# Sheet1.net
KiCad netlist of a schematic drawn in Altium Designer
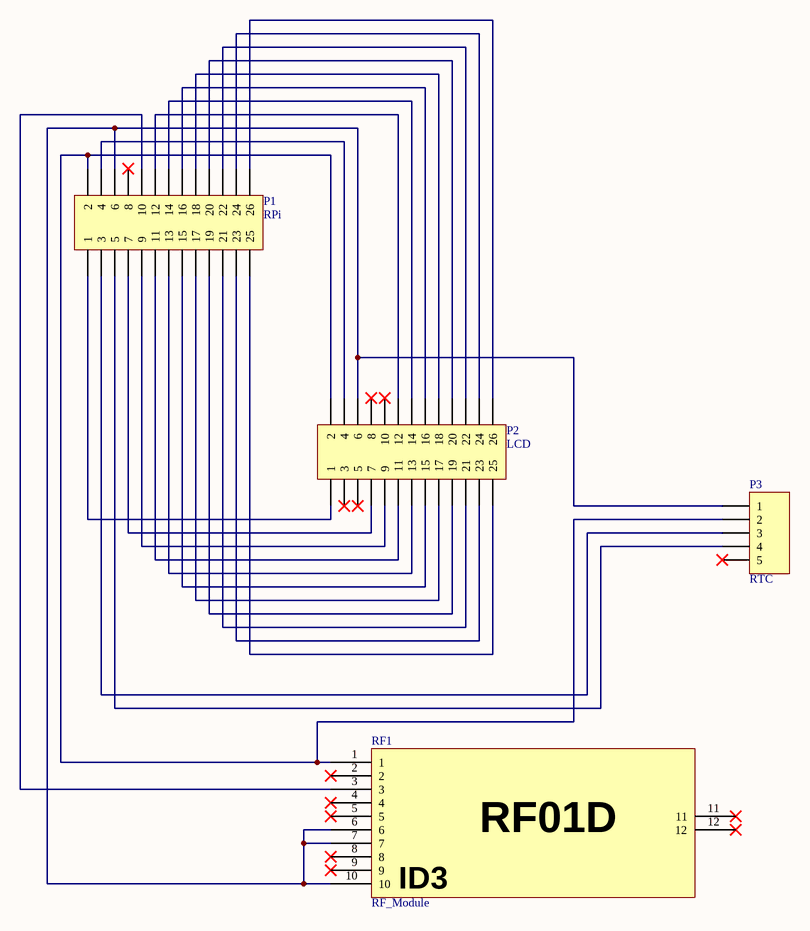
[diagram p0: Sheet1.SchDoc]

(export (version "E")
  (design (tool "Eeschema 10.0.6"))
  (components
    (comp (ref "P1")
      (value "RPi")
      (footprint "HDR2X13")
      (description "Header, 13-Pin, Dual row")
      (fields (field (name "PUBLISHER") "Altium Limited"))
      (libsource (lib "Miscellaneous Connectors") (part "Header 13X2"))
    )
    (comp (ref "P2")
      (value "LCD")
      (footprint "HDR2X13")
      (description "Header, 13-Pin, Dual row")
      (fields (field (name "PUBLISHER") "Altium Limited"))
      (libsource (lib "Miscellaneous Connectors") (part "Header 13X2"))
    )
    (comp (ref "P3")
      (value "RTC")
      (footprint "HDR1X5")
      (description "Header, 5-Pin")
      (fields (field (name "PUBLISHER") "Altium Limited"))
      (libsource (lib "Miscellaneous Connectors") (part "Header 5"))
    )
    (comp (ref "RF1")
      (value "RF_Module")
      (footprint "PcbLib1:PCBComponent_1")
      (libsource (lib "Schlib1") (part "Component_1"))
    )
  )
  (nets
    (net (code "1") (name "Net-(P1-Pad1)") (class "Default")
      (node (ref "P1") (pin "1") (pinfunction "1_1") (pintype "passive"))
      (node (ref "P2") (pin "1") (pinfunction "1_1") (pintype "passive"))
    )
    (net (code "2") (name "Net-(P1-Pad2)") (class "Default")
      (node (ref "P1") (pin "2") (pinfunction "2_2") (pintype "passive"))
      (node (ref "P2") (pin "2") (pinfunction "2_2") (pintype "passive"))
      (node (ref "P3") (pin "2") (pinfunction "2_2") (pintype "passive"))
      (node (ref "RF1") (pin "1") (pinfunction "1_1") (pintype "passive"))
    )
    (net (code "3") (name "Net-(P1-Pad3)") (class "Default")
      (node (ref "P1") (pin "3") (pinfunction "3_3") (pintype "passive"))
      (node (ref "P3") (pin "3") (pinfunction "3_3") (pintype "passive"))
    )
    (net (code "4") (name "Net-(P1-Pad4)") (class "Default")
      (node (ref "P1") (pin "4") (pinfunction "4_4") (pintype "passive"))
      (node (ref "P2") (pin "4") (pinfunction "4_4") (pintype "passive"))
    )
    (net (code "5") (name "Net-(P1-Pad5)") (class "Default")
      (node (ref "P1") (pin "5") (pinfunction "5_5") (pintype "passive"))
      (node (ref "P3") (pin "4") (pinfunction "4_4") (pintype "passive"))
    )
    (net (code "6") (name "Net-(P1-Pad6)") (class "Default")
      (node (ref "P1") (pin "6") (pinfunction "6_6") (pintype "passive"))
      (node (ref "P2") (pin "6") (pinfunction "6_6") (pintype "passive"))
      (node (ref "P3") (pin "1") (pinfunction "1_1") (pintype "passive"))
      (node (ref "RF1") (pin "10") (pinfunction "10_10") (pintype "passive"))
      (node (ref "RF1") (pin "6") (pinfunction "6_6") (pintype "passive"))
      (node (ref "RF1") (pin "7") (pinfunction "7_7") (pintype "passive"))
    )
    (net (code "7") (name "Net-(P1-Pad7)") (class "Default")
      (node (ref "P1") (pin "7") (pinfunction "7_7") (pintype "passive"))
      (node (ref "P2") (pin "7") (pinfunction "7_7") (pintype "passive"))
    )
    (net (code "8") (name "Net-(P1-Pad9)") (class "Default")
      (node (ref "P1") (pin "9") (pinfunction "9_9") (pintype "passive"))
      (node (ref "P2") (pin "9") (pinfunction "9_9") (pintype "passive"))
    )
    (net (code "9") (name "Net-(P1-Pad10)") (class "Default")
      (node (ref "P1") (pin "10") (pinfunction "10_10") (pintype "passive"))
      (node (ref "RF1") (pin "3") (pinfunction "3_3") (pintype "passive"))
    )
    (net (code "10") (name "Net-(P1-Pad11)") (class "Default")
      (node (ref "P1") (pin "11") (pinfunction "11_11") (pintype "passive"))
      (node (ref "P2") (pin "11") (pinfunction "11_11") (pintype "passive"))
    )
    (net (code "11") (name "Net-(P1-Pad12)") (class "Default")
      (node (ref "P1") (pin "12") (pinfunction "12_12") (pintype "passive"))
      (node (ref "P2") (pin "12") (pinfunction "12_12") (pintype "passive"))
    )
    (net (code "12") (name "Net-(P1-Pad13)") (class "Default")
      (node (ref "P1") (pin "13") (pinfunction "13_13") (pintype "passive"))
      (node (ref "P2") (pin "13") (pinfunction "13_13") (pintype "passive"))
    )
    (net (code "13") (name "Net-(P1-Pad14)") (class "Default")
      (node (ref "P1") (pin "14") (pinfunction "14_14") (pintype "passive"))
      (node (ref "P2") (pin "14") (pinfunction "14_14") (pintype "passive"))
    )
    (net (code "14") (name "Net-(P1-Pad15)") (class "Default")
      (node (ref "P1") (pin "15") (pinfunction "15_15") (pintype "passive"))
      (node (ref "P2") (pin "15") (pinfunction "15_15") (pintype "passive"))
    )
    (net (code "15") (name "Net-(P1-Pad16)") (class "Default")
      (node (ref "P1") (pin "16") (pinfunction "16_16") (pintype "passive"))
      (node (ref "P2") (pin "16") (pinfunction "16_16") (pintype "passive"))
    )
    (net (code "16") (name "Net-(P1-Pad17)") (class "Default")
      (node (ref "P1") (pin "17") (pinfunction "17_17") (pintype "passive"))
      (node (ref "P2") (pin "17") (pinfunction "17_17") (pintype "passive"))
    )
    (net (code "17") (name "Net-(P1-Pad18)") (class "Default")
      (node (ref "P1") (pin "18") (pinfunction "18_18") (pintype "passive"))
      (node (ref "P2") (pin "18") (pinfunction "18_18") (pintype "passive"))
    )
    (net (code "18") (name "Net-(P1-Pad19)") (class "Default")
      (node (ref "P1") (pin "19") (pinfunction "19_19") (pintype "passive"))
      (node (ref "P2") (pin "19") (pinfunction "19_19") (pintype "passive"))
    )
    (net (code "19") (name "Net-(P1-Pad20)") (class "Default")
      (node (ref "P1") (pin "20") (pinfunction "20_20") (pintype "passive"))
      (node (ref "P2") (pin "20") (pinfunction "20_20") (pintype "passive"))
    )
    (net (code "20") (name "Net-(P1-Pad21)") (class "Default")
      (node (ref "P1") (pin "21") (pinfunction "21_21") (pintype "passive"))
      (node (ref "P2") (pin "21") (pinfunction "21_21") (pintype "passive"))
    )
    (net (code "21") (name "Net-(P1-Pad22)") (class "Default")
      (node (ref "P1") (pin "22") (pinfunction "22_22") (pintype "passive"))
      (node (ref "P2") (pin "22") (pinfunction "22_22") (pintype "passive"))
    )
    (net (code "22") (name "Net-(P1-Pad23)") (class "Default")
      (node (ref "P1") (pin "23") (pinfunction "23_23") (pintype "passive"))
      (node (ref "P2") (pin "23") (pinfunction "23_23") (pintype "passive"))
    )
    (net (code "23") (name "Net-(P1-Pad24)") (class "Default")
      (node (ref "P1") (pin "24") (pinfunction "24_24") (pintype "passive"))
      (node (ref "P2") (pin "24") (pinfunction "24_24") (pintype "passive"))
    )
    (net (code "24") (name "Net-(P1-Pad25)") (class "Default")
      (node (ref "P1") (pin "25") (pinfunction "25_25") (pintype "passive"))
      (node (ref "P2") (pin "25") (pinfunction "25_25") (pintype "passive"))
    )
    (net (code "25") (name "Net-(P1-Pad26)") (class "Default")
      (node (ref "P1") (pin "26") (pinfunction "26_26") (pintype "passive"))
      (node (ref "P2") (pin "26") (pinfunction "26_26") (pintype "passive"))
    )
    (net (code "26") (name "unconnected-(P1-Pad8)") (class "Default")
      (node (ref "P1") (pin "8") (pinfunction "8_8") (pintype "passive+no_connect"))
    )
    (net (code "27") (name "unconnected-(P2-Pad3)") (class "Default")
      (node (ref "P2") (pin "3") (pinfunction "3_3") (pintype "passive+no_connect"))
    )
    (net (code "28") (name "unconnected-(P2-Pad5)") (class "Default")
      (node (ref "P2") (pin "5") (pinfunction "5_5") (pintype "passive+no_connect"))
    )
    (net (code "29") (name "unconnected-(P2-Pad8)") (class "Default")
      (node (ref "P2") (pin "8") (pinfunction "8_8") (pintype "passive+no_connect"))
    )
    (net (code "30") (name "unconnected-(P2-Pad10)") (class "Default")
      (node (ref "P2") (pin "10") (pinfunction "10_10") (pintype "passive+no_connect"))
    )
    (net (code "31") (name "unconnected-(P3-Pad5)") (class "Default")
      (node (ref "P3") (pin "5") (pinfunction "5_5") (pintype "passive+no_connect"))
    )
    (net (code "32") (name "unconnected-(RF1-Pad2)") (class "Default")
      (node (ref "RF1") (pin "2") (pinfunction "2_2") (pintype "passive+no_connect"))
    )
    (net (code "33") (name "unconnected-(RF1-Pad4)") (class "Default")
      (node (ref "RF1") (pin "4") (pinfunction "4_4") (pintype "passive+no_connect"))
    )
    (net (code "34") (name "unconnected-(RF1-Pad5)") (class "Default")
      (node (ref "RF1") (pin "5") (pinfunction "5_5") (pintype "passive+no_connect"))
    )
    (net (code "35") (name "unconnected-(RF1-Pad8)") (class "Default")
      (node (ref "RF1") (pin "8") (pinfunction "8_8") (pintype "passive+no_connect"))
    )
    (net (code "36") (name "unconnected-(RF1-Pad9)") (class "Default")
      (node (ref "RF1") (pin "9") (pinfunction "9_9") (pintype "passive+no_connect"))
    )
    (net (code "37") (name "unconnected-(RF1-Pad11)") (class "Default")
      (node (ref "RF1") (pin "11") (pinfunction "11_11") (pintype "passive+no_connect"))
    )
    (net (code "38") (name "unconnected-(RF1-Pad12)") (class "Default")
      (node (ref "RF1") (pin "12") (pinfunction "12_12") (pintype "passive+no_connect"))
    )
  )
)
